# POVWand16.net
KiCad netlist of a schematic drawn in EAGLE
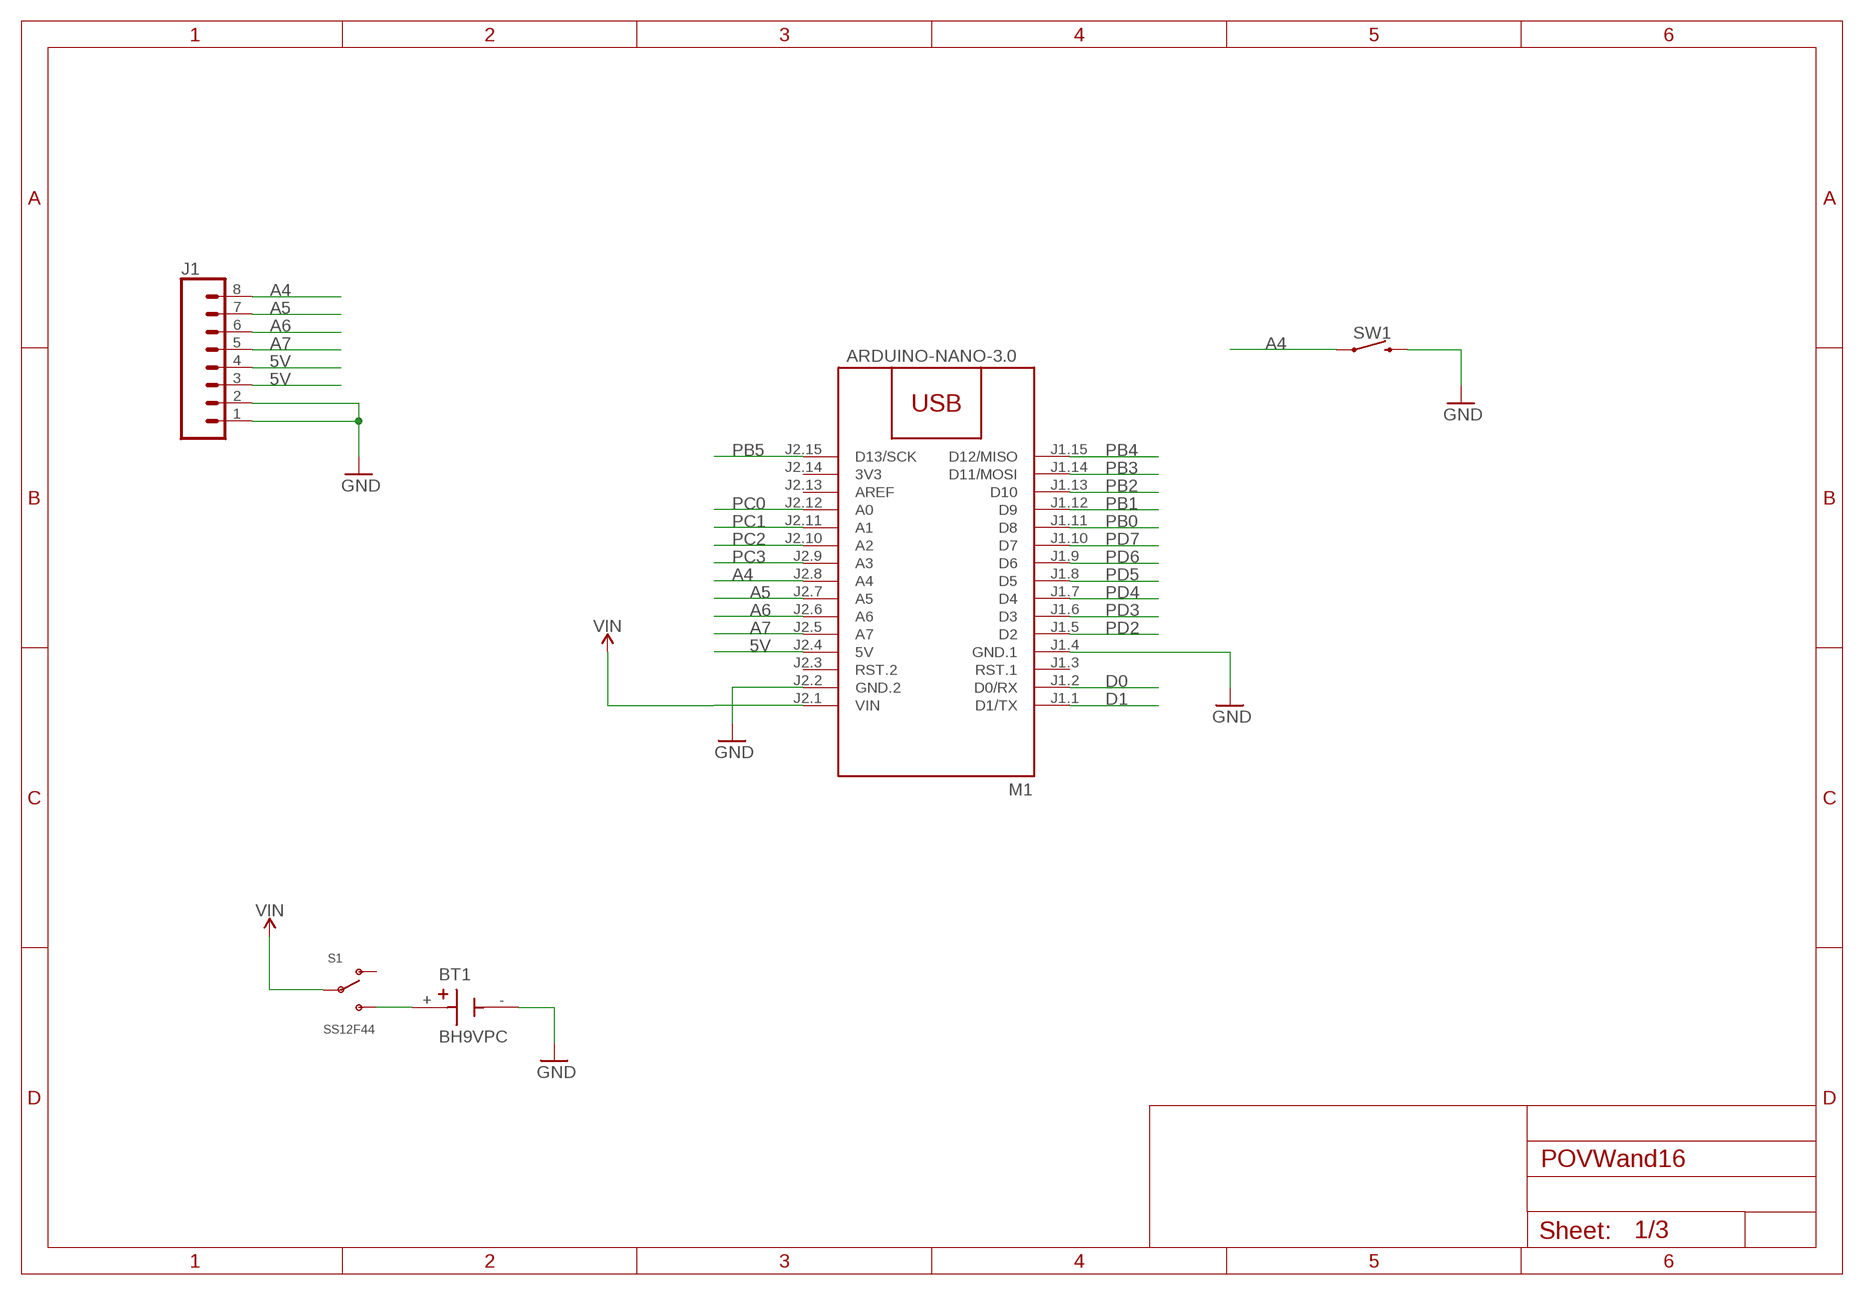
[diagram p0: schematic, sheet 1]
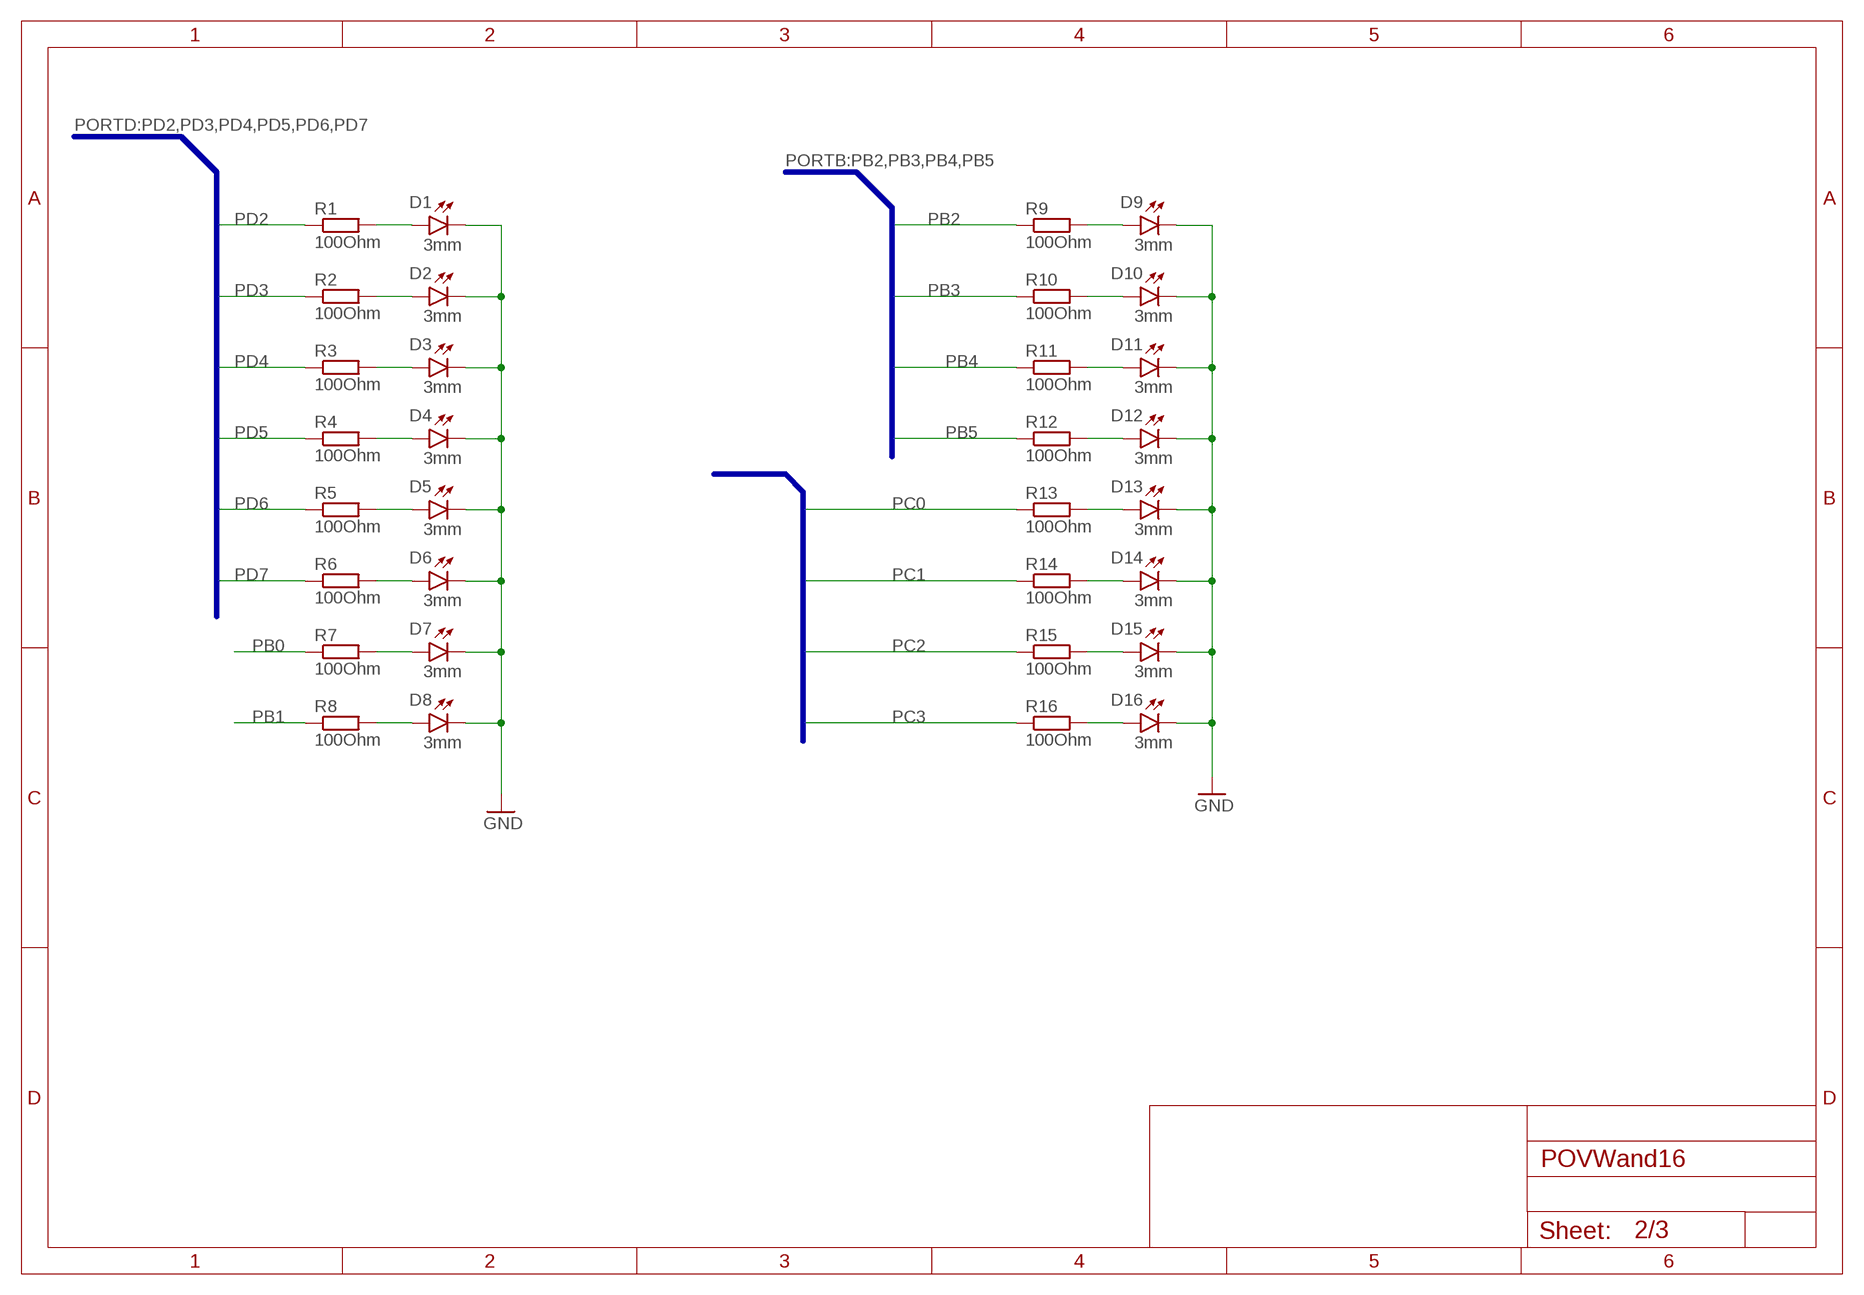
[diagram p1: schematic, sheet 2]
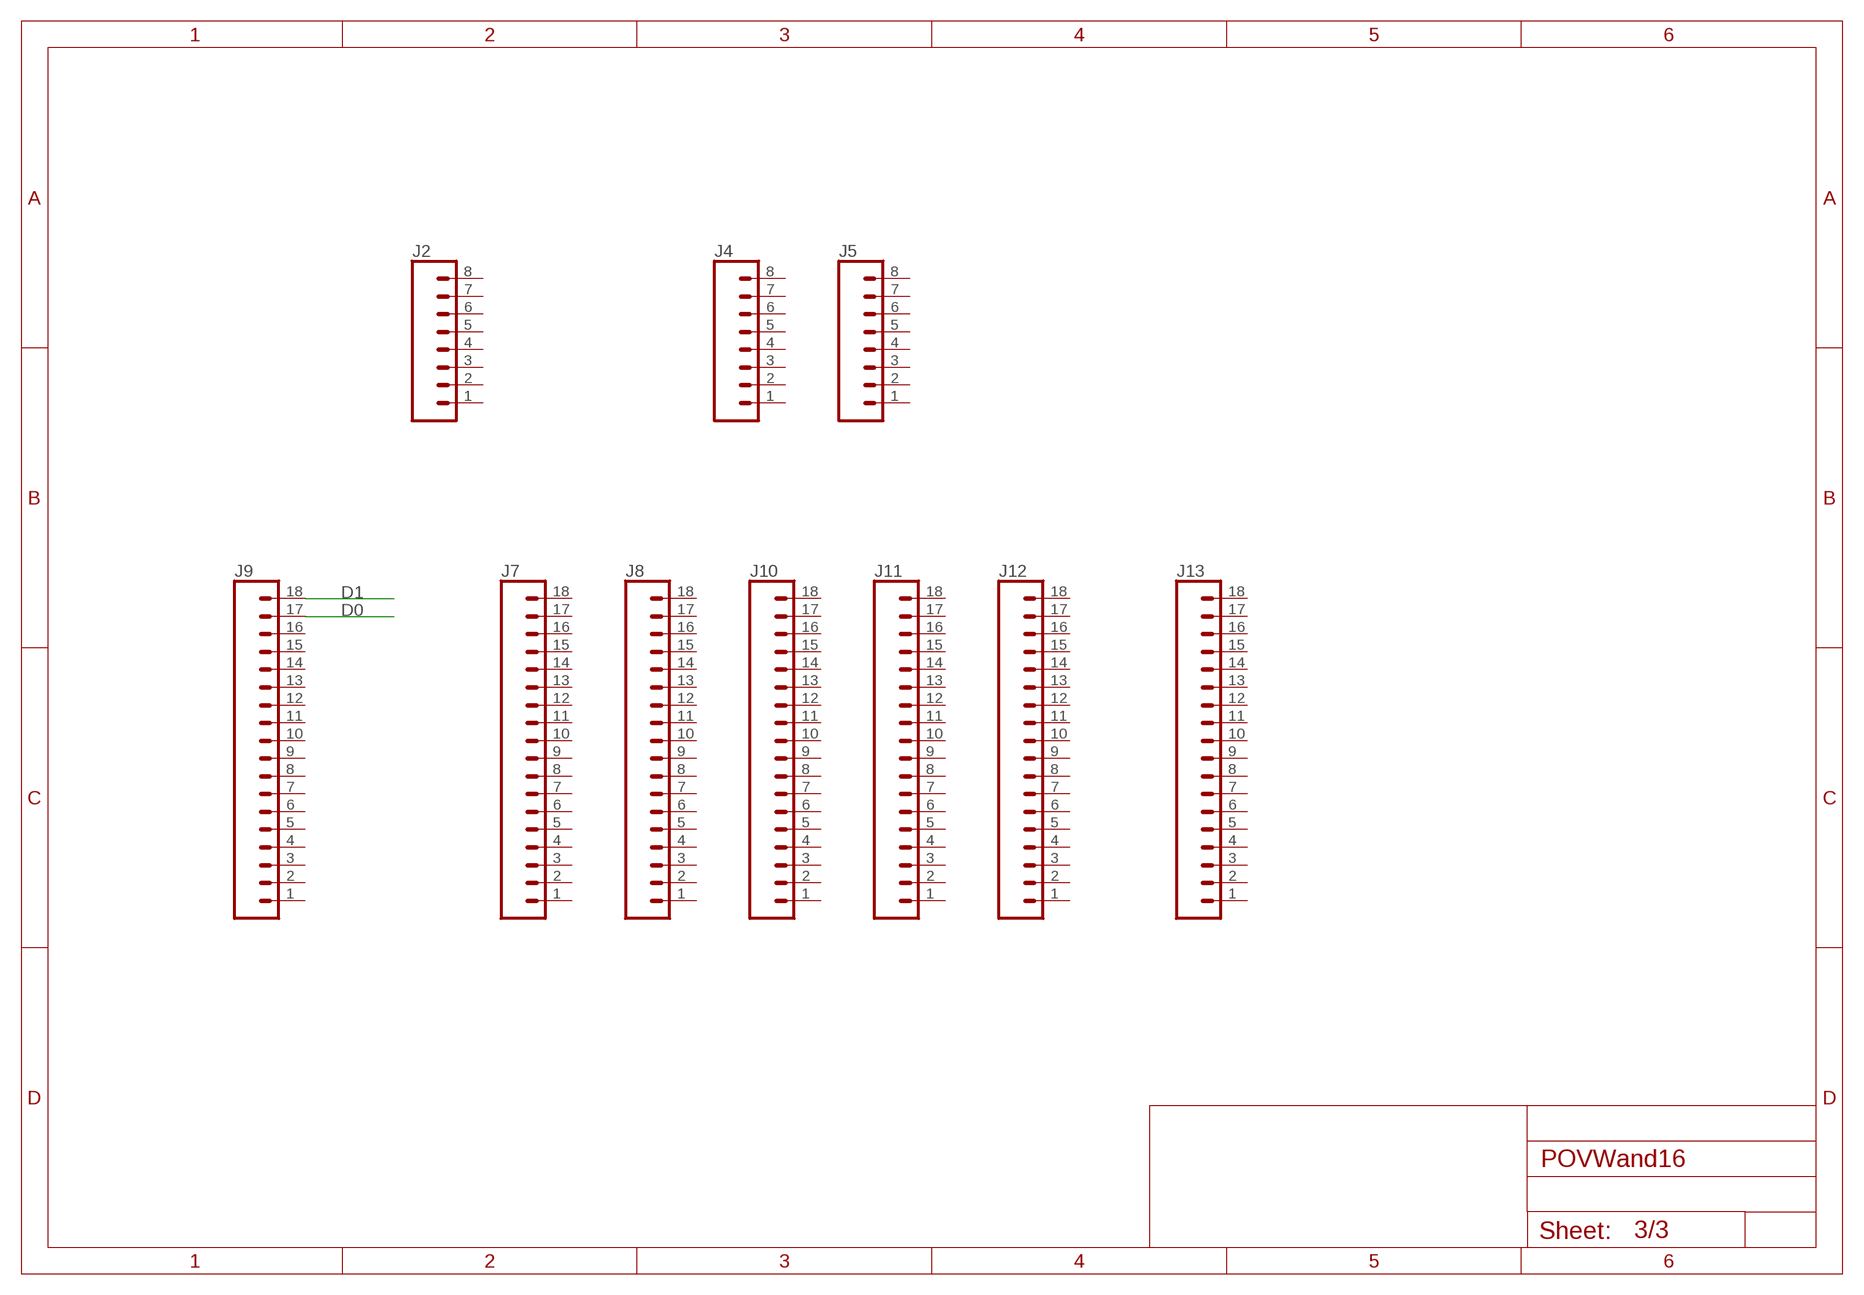
[diagram p2: schematic, sheet 3]

(export (version "E")
  (design (tool "Eeschema 10.0.6"))
  (components
    (comp (ref "BT1")
      (value "BH9VPC")
      (footprint "eagle-import:BAT_BH9VPC")
      (fields (field (name "MF") "MPD _Memory"))
      (libsource (lib "eagle-import") (part "BH9VPC"))
    )
    (comp (ref "J1")
      (value "CONN_08\"")
      (footprint "eagle-import:1X08")
      (libsource (lib "eagle-import") (part "CONN_08{dblquote}"))
    )
    (comp (ref "M1")
      (value "ARDUINO-NANO-3.0")
      (footprint "eagle-import:ARDUINO-NANO-3.0")
      (libsource (lib "eagle-import") (part "ARDUINO-NANO-3.0"))
    )
    (comp (ref "S1")
      (value "SS12F44")
      (footprint "eagle-import:SS12F44G5")
      (fields (field (name "MPN") "SS12F44G5"))
      (libsource (lib "eagle-import") (part "SS12F44"))
    )
    (comp (ref "SW1")
      (value "MOMENTARY-SWITCH-SPST_6X6MM")
      (footprint "eagle-import:TACT_SW_PTH_6.0MM")
      (fields (field (name "MF") "C&K") (field (name "MPN") "PTS645SM43-2 LFS"))
      (libsource (lib "eagle-import") (part "MOMENTARY-SWITCH-SPST_6X6MM"))
    )
    (comp (ref "J2")
      (value "CONN_08\"")
      (footprint "eagle-import:1X08")
      (libsource (lib "eagle-import") (part "CONN_08{dblquote}"))
    )
    (comp (ref "J4")
      (value "CONN_08\"")
      (footprint "eagle-import:1X08")
      (libsource (lib "eagle-import") (part "CONN_08{dblquote}"))
    )
    (comp (ref "J5")
      (value "CONN_08\"")
      (footprint "eagle-import:1X08")
      (libsource (lib "eagle-import") (part "CONN_08{dblquote}"))
    )
    (comp (ref "J7")
      (value "CONN_18")
      (footprint "eagle-import:1X18")
      (libsource (lib "eagle-import") (part "CONN_18"))
    )
    (comp (ref "J8")
      (value "CONN_18")
      (footprint "eagle-import:1X18")
      (libsource (lib "eagle-import") (part "CONN_18"))
    )
    (comp (ref "J9")
      (value "CONN_18")
      (footprint "eagle-import:1X18")
      (libsource (lib "eagle-import") (part "CONN_18"))
    )
    (comp (ref "J10")
      (value "CONN_18")
      (footprint "eagle-import:1X18")
      (libsource (lib "eagle-import") (part "CONN_18"))
    )
    (comp (ref "J11")
      (value "CONN_18")
      (footprint "eagle-import:1X18")
      (libsource (lib "eagle-import") (part "CONN_18"))
    )
    (comp (ref "J12")
      (value "CONN_18")
      (footprint "eagle-import:1X18")
      (libsource (lib "eagle-import") (part "CONN_18"))
    )
    (comp (ref "J13")
      (value "CONN_18")
      (footprint "eagle-import:1X18")
      (libsource (lib "eagle-import") (part "CONN_18"))
    )
    (comp (ref "D1")
      (value "3mm")
      (footprint "eagle-import:LED3MM")
      (libsource (lib "eagle-import") (part "LED_T/H_RADIAL_3MM"))
    )
    (comp (ref "D2")
      (value "3mm")
      (footprint "eagle-import:LED3MM")
      (libsource (lib "eagle-import") (part "LED_T/H_RADIAL_3MM"))
    )
    (comp (ref "D3")
      (value "3mm")
      (footprint "eagle-import:LED3MM")
      (libsource (lib "eagle-import") (part "LED_T/H_RADIAL_3MM"))
    )
    (comp (ref "D4")
      (value "3mm")
      (footprint "eagle-import:LED3MM")
      (libsource (lib "eagle-import") (part "LED_T/H_RADIAL_3MM"))
    )
    (comp (ref "D5")
      (value "3mm")
      (footprint "eagle-import:LED3MM")
      (libsource (lib "eagle-import") (part "LED_T/H_RADIAL_3MM"))
    )
    (comp (ref "D6")
      (value "3mm")
      (footprint "eagle-import:LED3MM")
      (libsource (lib "eagle-import") (part "LED_T/H_RADIAL_3MM"))
    )
    (comp (ref "D7")
      (value "3mm")
      (footprint "eagle-import:LED3MM")
      (libsource (lib "eagle-import") (part "LED_T/H_RADIAL_3MM"))
    )
    (comp (ref "D8")
      (value "3mm")
      (footprint "eagle-import:LED3MM")
      (libsource (lib "eagle-import") (part "LED_T/H_RADIAL_3MM"))
    )
    (comp (ref "D9")
      (value "3mm")
      (footprint "eagle-import:LED3MM")
      (libsource (lib "eagle-import") (part "LED_T/H_RADIAL_3MM"))
    )
    (comp (ref "D10")
      (value "3mm")
      (footprint "eagle-import:LED3MM")
      (libsource (lib "eagle-import") (part "LED_T/H_RADIAL_3MM"))
    )
    (comp (ref "D11")
      (value "3mm")
      (footprint "eagle-import:LED3MM")
      (libsource (lib "eagle-import") (part "LED_T/H_RADIAL_3MM"))
    )
    (comp (ref "D12")
      (value "3mm")
      (footprint "eagle-import:LED3MM")
      (libsource (lib "eagle-import") (part "LED_T/H_RADIAL_3MM"))
    )
    (comp (ref "D13")
      (value "3mm")
      (footprint "eagle-import:LED3MM")
      (libsource (lib "eagle-import") (part "LED_T/H_RADIAL_3MM"))
    )
    (comp (ref "D14")
      (value "3mm")
      (footprint "eagle-import:LED3MM")
      (libsource (lib "eagle-import") (part "LED_T/H_RADIAL_3MM"))
    )
    (comp (ref "D15")
      (value "3mm")
      (footprint "eagle-import:LED3MM")
      (libsource (lib "eagle-import") (part "LED_T/H_RADIAL_3MM"))
    )
    (comp (ref "D16")
      (value "3mm")
      (footprint "eagle-import:LED3MM")
      (libsource (lib "eagle-import") (part "LED_T/H_RADIAL_3MM"))
    )
    (comp (ref "R1")
      (value "100Ohm")
      (footprint "eagle-import:0207_7")
      (libsource (lib "eagle-import") (part "100R_RESISTOR_T/H_0207/7"))
    )
    (comp (ref "R2")
      (value "100Ohm")
      (footprint "eagle-import:0207_7")
      (libsource (lib "eagle-import") (part "100R_RESISTOR_T/H_0207/7"))
    )
    (comp (ref "R3")
      (value "100Ohm")
      (footprint "eagle-import:0207_7")
      (libsource (lib "eagle-import") (part "100R_RESISTOR_T/H_0207/7"))
    )
    (comp (ref "R4")
      (value "100Ohm")
      (footprint "eagle-import:0207_7")
      (libsource (lib "eagle-import") (part "100R_RESISTOR_T/H_0207/7"))
    )
    (comp (ref "R5")
      (value "100Ohm")
      (footprint "eagle-import:0207_7")
      (libsource (lib "eagle-import") (part "100R_RESISTOR_T/H_0207/7"))
    )
    (comp (ref "R6")
      (value "100Ohm")
      (footprint "eagle-import:0207_7")
      (libsource (lib "eagle-import") (part "100R_RESISTOR_T/H_0207/7"))
    )
    (comp (ref "R7")
      (value "100Ohm")
      (footprint "eagle-import:0207_7")
      (libsource (lib "eagle-import") (part "100R_RESISTOR_T/H_0207/7"))
    )
    (comp (ref "R8")
      (value "100Ohm")
      (footprint "eagle-import:0207_7")
      (libsource (lib "eagle-import") (part "100R_RESISTOR_T/H_0207/7"))
    )
    (comp (ref "R9")
      (value "100Ohm")
      (footprint "eagle-import:0207_7")
      (libsource (lib "eagle-import") (part "100R_RESISTOR_T/H_0207/7"))
    )
    (comp (ref "R10")
      (value "100Ohm")
      (footprint "eagle-import:0207_7")
      (libsource (lib "eagle-import") (part "100R_RESISTOR_T/H_0207/7"))
    )
    (comp (ref "R11")
      (value "100Ohm")
      (footprint "eagle-import:0207_7")
      (libsource (lib "eagle-import") (part "100R_RESISTOR_T/H_0207/7"))
    )
    (comp (ref "R12")
      (value "100Ohm")
      (footprint "eagle-import:0207_7")
      (libsource (lib "eagle-import") (part "100R_RESISTOR_T/H_0207/7"))
    )
    (comp (ref "R13")
      (value "100Ohm")
      (footprint "eagle-import:0207_7")
      (libsource (lib "eagle-import") (part "100R_RESISTOR_T/H_0207/7"))
    )
    (comp (ref "R14")
      (value "100Ohm")
      (footprint "eagle-import:0207_7")
      (libsource (lib "eagle-import") (part "100R_RESISTOR_T/H_0207/7"))
    )
    (comp (ref "R15")
      (value "100Ohm")
      (footprint "eagle-import:0207_7")
      (libsource (lib "eagle-import") (part "100R_RESISTOR_T/H_0207/7"))
    )
    (comp (ref "R16")
      (value "100Ohm")
      (footprint "eagle-import:0207_7")
      (libsource (lib "eagle-import") (part "100R_RESISTOR_T/H_0207/7"))
    )
  )
  (nets
    (net (code "5") (name "3V3") (class "Default")
      (node (ref "M1") (pin "J2.14") (pinfunction "3V3_J2.14") (pintype "power_in"))
    )
    (net (code "6") (name "5V") (class "Default")
      (node (ref "J1") (pin "3") (pinfunction "3_3") (pintype "passive"))
      (node (ref "J1") (pin "4") (pinfunction "4_4") (pintype "passive"))
      (node (ref "M1") (pin "J2.4") (pinfunction "5V_J2.4") (pintype "power_in"))
    )
    (net (code "7") (name "A4") (class "Default")
      (node (ref "J1") (pin "8") (pinfunction "8_8") (pintype "passive"))
      (node (ref "M1") (pin "J2.8") (pinfunction "A4_J2.8") (pintype "bidirectional"))
      (node (ref "SW1") (pin "1") (pinfunction "1_1") (pintype "passive"))
      (node (ref "SW1") (pin "2") (pinfunction "1_2") (pintype "passive"))
    )
    (net (code "8") (name "A5") (class "Default")
      (node (ref "J1") (pin "7") (pinfunction "7_7") (pintype "passive"))
      (node (ref "M1") (pin "J2.7") (pinfunction "A5_J2.7") (pintype "bidirectional"))
    )
    (net (code "9") (name "A6") (class "Default")
      (node (ref "J1") (pin "6") (pinfunction "6_6") (pintype "passive"))
      (node (ref "M1") (pin "J2.6") (pinfunction "A6_J2.6") (pintype "bidirectional"))
    )
    (net (code "10") (name "A7") (class "Default")
      (node (ref "J1") (pin "5") (pinfunction "5_5") (pintype "passive"))
      (node (ref "M1") (pin "J2.5") (pinfunction "A7_J2.5") (pintype "bidirectional"))
    )
    (net (code "11") (name "D0") (class "Default")
      (node (ref "J9") (pin "17") (pinfunction "17_17") (pintype "passive"))
      (node (ref "M1") (pin "J1.2") (pinfunction "D0/RX_J1.2") (pintype "bidirectional"))
    )
    (net (code "12") (name "D1") (class "Default")
      (node (ref "J9") (pin "18") (pinfunction "18_18") (pintype "passive"))
      (node (ref "M1") (pin "J1.1") (pinfunction "D1/TX_J1.1") (pintype "bidirectional"))
    )
    (net (code "13") (name "GND") (class "Default")
      (node (ref "BT1") (pin "-") (pinfunction "-_-") (pintype "passive"))
      (node (ref "D1") (pin "K") (pinfunction "C_K") (pintype "passive"))
      (node (ref "D10") (pin "K") (pinfunction "C_K") (pintype "passive"))
      (node (ref "D11") (pin "K") (pinfunction "C_K") (pintype "passive"))
      (node (ref "D12") (pin "K") (pinfunction "C_K") (pintype "passive"))
      (node (ref "D13") (pin "K") (pinfunction "C_K") (pintype "passive"))
      (node (ref "D14") (pin "K") (pinfunction "C_K") (pintype "passive"))
      (node (ref "D15") (pin "K") (pinfunction "C_K") (pintype "passive"))
      (node (ref "D16") (pin "K") (pinfunction "C_K") (pintype "passive"))
      (node (ref "D2") (pin "K") (pinfunction "C_K") (pintype "passive"))
      (node (ref "D3") (pin "K") (pinfunction "C_K") (pintype "passive"))
      (node (ref "D4") (pin "K") (pinfunction "C_K") (pintype "passive"))
      (node (ref "D5") (pin "K") (pinfunction "C_K") (pintype "passive"))
      (node (ref "D6") (pin "K") (pinfunction "C_K") (pintype "passive"))
      (node (ref "D7") (pin "K") (pinfunction "C_K") (pintype "passive"))
      (node (ref "D8") (pin "K") (pinfunction "C_K") (pintype "passive"))
      (node (ref "D9") (pin "K") (pinfunction "C_K") (pintype "passive"))
      (node (ref "J1") (pin "1") (pinfunction "1_1") (pintype "passive"))
      (node (ref "J1") (pin "2") (pinfunction "2_2") (pintype "passive"))
      (node (ref "M1") (pin "J1.4") (pinfunction "GND.1_J1.4") (pintype "power_in"))
      (node (ref "M1") (pin "J2.2") (pinfunction "GND.2_J2.2") (pintype "power_in"))
      (node (ref "SW1") (pin "3") (pinfunction "2_3") (pintype "passive"))
      (node (ref "SW1") (pin "4") (pinfunction "2_4") (pintype "passive"))
    )
    (net (code "14") (name "Net-(D1-PadA)") (class "Default")
      (node (ref "D1") (pin "A") (pinfunction "A_A") (pintype "passive"))
      (node (ref "R1") (pin "2") (pinfunction "2_2") (pintype "passive"))
    )
    (net (code "15") (name "Net-(D2-PadA)") (class "Default")
      (node (ref "D2") (pin "A") (pinfunction "A_A") (pintype "passive"))
      (node (ref "R2") (pin "2") (pinfunction "2_2") (pintype "passive"))
    )
    (net (code "16") (name "Net-(D3-PadA)") (class "Default")
      (node (ref "D3") (pin "A") (pinfunction "A_A") (pintype "passive"))
      (node (ref "R3") (pin "2") (pinfunction "2_2") (pintype "passive"))
    )
    (net (code "17") (name "Net-(D4-PadA)") (class "Default")
      (node (ref "D4") (pin "A") (pinfunction "A_A") (pintype "passive"))
      (node (ref "R4") (pin "2") (pinfunction "2_2") (pintype "passive"))
    )
    (net (code "18") (name "Net-(D5-PadA)") (class "Default")
      (node (ref "D5") (pin "A") (pinfunction "A_A") (pintype "passive"))
      (node (ref "R5") (pin "2") (pinfunction "2_2") (pintype "passive"))
    )
    (net (code "19") (name "Net-(D6-PadA)") (class "Default")
      (node (ref "D6") (pin "A") (pinfunction "A_A") (pintype "passive"))
      (node (ref "R6") (pin "2") (pinfunction "2_2") (pintype "passive"))
    )
    (net (code "20") (name "Net-(D7-PadA)") (class "Default")
      (node (ref "D7") (pin "A") (pinfunction "A_A") (pintype "passive"))
      (node (ref "R7") (pin "2") (pinfunction "2_2") (pintype "passive"))
    )
    (net (code "21") (name "Net-(D8-PadA)") (class "Default")
      (node (ref "D8") (pin "A") (pinfunction "A_A") (pintype "passive"))
      (node (ref "R8") (pin "2") (pinfunction "2_2") (pintype "passive"))
    )
    (net (code "22") (name "Net-(D9-PadA)") (class "Default")
      (node (ref "D9") (pin "A") (pinfunction "A_A") (pintype "passive"))
      (node (ref "R9") (pin "2") (pinfunction "2_2") (pintype "passive"))
    )
    (net (code "23") (name "Net-(D10-PadA)") (class "Default")
      (node (ref "D10") (pin "A") (pinfunction "A_A") (pintype "passive"))
      (node (ref "R10") (pin "2") (pinfunction "2_2") (pintype "passive"))
    )
    (net (code "24") (name "Net-(D11-PadA)") (class "Default")
      (node (ref "D11") (pin "A") (pinfunction "A_A") (pintype "passive"))
      (node (ref "R11") (pin "2") (pinfunction "2_2") (pintype "passive"))
    )
    (net (code "25") (name "Net-(D12-PadA)") (class "Default")
      (node (ref "D12") (pin "A") (pinfunction "A_A") (pintype "passive"))
      (node (ref "R12") (pin "2") (pinfunction "2_2") (pintype "passive"))
    )
    (net (code "26") (name "Net-(D13-PadA)") (class "Default")
      (node (ref "D13") (pin "A") (pinfunction "A_A") (pintype "passive"))
      (node (ref "R13") (pin "2") (pinfunction "2_2") (pintype "passive"))
    )
    (net (code "27") (name "Net-(D14-PadA)") (class "Default")
      (node (ref "D14") (pin "A") (pinfunction "A_A") (pintype "passive"))
      (node (ref "R14") (pin "2") (pinfunction "2_2") (pintype "passive"))
    )
    (net (code "28") (name "Net-(D15-PadA)") (class "Default")
      (node (ref "D15") (pin "A") (pinfunction "A_A") (pintype "passive"))
      (node (ref "R15") (pin "2") (pinfunction "2_2") (pintype "passive"))
    )
    (net (code "29") (name "Net-(D16-PadA)") (class "Default")
      (node (ref "D16") (pin "A") (pinfunction "A_A") (pintype "passive"))
      (node (ref "R16") (pin "2") (pinfunction "2_2") (pintype "passive"))
    )
    (net (code "30") (name "Net-(S1-S)") (class "Default")
      (node (ref "BT1") (pin "+") (pinfunction "+_+") (pintype "passive"))
      (node (ref "S1") (pin "3") (pinfunction "S_3") (pintype "passive"))
    )
    (net (code "31") (name "PB0") (class "Default")
      (node (ref "M1") (pin "J1.11") (pinfunction "D8_J1.11") (pintype "bidirectional"))
      (node (ref "R7") (pin "1") (pinfunction "1_1") (pintype "passive"))
    )
    (net (code "32") (name "PB1") (class "Default")
      (node (ref "M1") (pin "J1.12") (pinfunction "D9_J1.12") (pintype "bidirectional"))
      (node (ref "R8") (pin "1") (pinfunction "1_1") (pintype "passive"))
    )
    (net (code "33") (name "PB2") (class "Default")
      (node (ref "M1") (pin "J1.13") (pinfunction "D10_J1.13") (pintype "bidirectional"))
      (node (ref "R9") (pin "1") (pinfunction "1_1") (pintype "passive"))
    )
    (net (code "34") (name "PB3") (class "Default")
      (node (ref "M1") (pin "J1.14") (pinfunction "D11/MOSI_J1.14") (pintype "bidirectional"))
      (node (ref "R10") (pin "1") (pinfunction "1_1") (pintype "passive"))
    )
    (net (code "35") (name "PB4") (class "Default")
      (node (ref "M1") (pin "J1.15") (pinfunction "D12/MISO_J1.15") (pintype "bidirectional"))
      (node (ref "R11") (pin "1") (pinfunction "1_1") (pintype "passive"))
    )
    (net (code "36") (name "PB5") (class "Default")
      (node (ref "M1") (pin "J2.15") (pinfunction "D13/SCK_J2.15") (pintype "bidirectional"))
      (node (ref "R12") (pin "1") (pinfunction "1_1") (pintype "passive"))
    )
    (net (code "37") (name "PC0") (class "Default")
      (node (ref "M1") (pin "J2.12") (pinfunction "A0_J2.12") (pintype "bidirectional"))
      (node (ref "R13") (pin "1") (pinfunction "1_1") (pintype "passive"))
    )
    (net (code "38") (name "PC1") (class "Default")
      (node (ref "M1") (pin "J2.11") (pinfunction "A1_J2.11") (pintype "bidirectional"))
      (node (ref "R14") (pin "1") (pinfunction "1_1") (pintype "passive"))
    )
    (net (code "39") (name "PC2") (class "Default")
      (node (ref "M1") (pin "J2.10") (pinfunction "A2_J2.10") (pintype "bidirectional"))
      (node (ref "R15") (pin "1") (pinfunction "1_1") (pintype "passive"))
    )
    (net (code "40") (name "PC3") (class "Default")
      (node (ref "M1") (pin "J2.9") (pinfunction "A3_J2.9") (pintype "bidirectional"))
      (node (ref "R16") (pin "1") (pinfunction "1_1") (pintype "passive"))
    )
    (net (code "41") (name "PD2") (class "Default")
      (node (ref "M1") (pin "J1.5") (pinfunction "D2_J1.5") (pintype "bidirectional"))
      (node (ref "R1") (pin "1") (pinfunction "1_1") (pintype "passive"))
    )
    (net (code "42") (name "PD3") (class "Default")
      (node (ref "M1") (pin "J1.6") (pinfunction "D3_J1.6") (pintype "bidirectional"))
      (node (ref "R2") (pin "1") (pinfunction "1_1") (pintype "passive"))
    )
    (net (code "43") (name "PD4") (class "Default")
      (node (ref "M1") (pin "J1.7") (pinfunction "D4_J1.7") (pintype "bidirectional"))
      (node (ref "R3") (pin "1") (pinfunction "1_1") (pintype "passive"))
    )
    (net (code "44") (name "PD5") (class "Default")
      (node (ref "M1") (pin "J1.8") (pinfunction "D5_J1.8") (pintype "bidirectional"))
      (node (ref "R4") (pin "1") (pinfunction "1_1") (pintype "passive"))
    )
    (net (code "45") (name "PD6") (class "Default")
      (node (ref "M1") (pin "J1.9") (pinfunction "D6_J1.9") (pintype "bidirectional"))
      (node (ref "R5") (pin "1") (pinfunction "1_1") (pintype "passive"))
    )
    (net (code "46") (name "PD7") (class "Default")
      (node (ref "M1") (pin "J1.10") (pinfunction "D7_J1.10") (pintype "bidirectional"))
      (node (ref "R6") (pin "1") (pinfunction "1_1") (pintype "passive"))
    )
    (net (code "47") (name "VIN") (class "Default")
      (node (ref "M1") (pin "J2.1") (pinfunction "VIN_J2.1") (pintype "power_in"))
      (node (ref "S1") (pin "2") (pinfunction "P_2") (pintype "passive"))
    )
    (net (code "48") (name "unconnected-(J2-Pad1)") (class "Default")
      (node (ref "J2") (pin "1") (pinfunction "1_1") (pintype "passive"))
    )
    (net (code "49") (name "unconnected-(J2-Pad2)") (class "Default")
      (node (ref "J2") (pin "2") (pinfunction "2_2") (pintype "passive"))
    )
    (net (code "50") (name "unconnected-(J2-Pad3)") (class "Default")
      (node (ref "J2") (pin "3") (pinfunction "3_3") (pintype "passive"))
    )
    (net (code "51") (name "unconnected-(J2-Pad4)") (class "Default")
      (node (ref "J2") (pin "4") (pinfunction "4_4") (pintype "passive"))
    )
    (net (code "52") (name "unconnected-(J2-Pad5)") (class "Default")
      (node (ref "J2") (pin "5") (pinfunction "5_5") (pintype "passive"))
    )
    (net (code "53") (name "unconnected-(J2-Pad6)") (class "Default")
      (node (ref "J2") (pin "6") (pinfunction "6_6") (pintype "passive"))
    )
    (net (code "54") (name "unconnected-(J2-Pad7)") (class "Default")
      (node (ref "J2") (pin "7") (pinfunction "7_7") (pintype "passive"))
    )
    (net (code "55") (name "unconnected-(J2-Pad8)") (class "Default")
      (node (ref "J2") (pin "8") (pinfunction "8_8") (pintype "passive"))
    )
    (net (code "56") (name "unconnected-(J4-Pad1)") (class "Default")
      (node (ref "J4") (pin "1") (pinfunction "1_1") (pintype "passive"))
    )
    (net (code "57") (name "unconnected-(J4-Pad2)") (class "Default")
      (node (ref "J4") (pin "2") (pinfunction "2_2") (pintype "passive"))
    )
    (net (code "58") (name "unconnected-(J4-Pad3)") (class "Default")
      (node (ref "J4") (pin "3") (pinfunction "3_3") (pintype "passive"))
    )
    (net (code "59") (name "unconnected-(J4-Pad4)") (class "Default")
      (node (ref "J4") (pin "4") (pinfunction "4_4") (pintype "passive"))
    )
    (net (code "60") (name "unconnected-(J4-Pad5)") (class "Default")
      (node (ref "J4") (pin "5") (pinfunction "5_5") (pintype "passive"))
    )
    (net (code "61") (name "unconnected-(J4-Pad6)") (class "Default")
      (node (ref "J4") (pin "6") (pinfunction "6_6") (pintype "passive"))
    )
    (net (code "62") (name "unconnected-(J4-Pad7)") (class "Default")
      (node (ref "J4") (pin "7") (pinfunction "7_7") (pintype "passive"))
    )
    (net (code "63") (name "unconnected-(J4-Pad8)") (class "Default")
      (node (ref "J4") (pin "8") (pinfunction "8_8") (pintype "passive"))
    )
    (net (code "64") (name "unconnected-(J5-Pad1)") (class "Default")
      (node (ref "J5") (pin "1") (pinfunction "1_1") (pintype "passive"))
    )
    (net (code "65") (name "unconnected-(J5-Pad2)") (class "Default")
      (node (ref "J5") (pin "2") (pinfunction "2_2") (pintype "passive"))
    )
    (net (code "66") (name "unconnected-(J5-Pad3)") (class "Default")
      (node (ref "J5") (pin "3") (pinfunction "3_3") (pintype "passive"))
    )
    (net (code "67") (name "unconnected-(J5-Pad4)") (class "Default")
      (node (ref "J5") (pin "4") (pinfunction "4_4") (pintype "passive"))
    )
    (net (code "68") (name "unconnected-(J5-Pad5)") (class "Default")
      (node (ref "J5") (pin "5") (pinfunction "5_5") (pintype "passive"))
    )
    (net (code "69") (name "unconnected-(J5-Pad6)") (class "Default")
      (node (ref "J5") (pin "6") (pinfunction "6_6") (pintype "passive"))
    )
    (net (code "70") (name "unconnected-(J5-Pad7)") (class "Default")
      (node (ref "J5") (pin "7") (pinfunction "7_7") (pintype "passive"))
    )
    (net (code "71") (name "unconnected-(J5-Pad8)") (class "Default")
      (node (ref "J5") (pin "8") (pinfunction "8_8") (pintype "passive"))
    )
    (net (code "72") (name "unconnected-(J7-Pad1)") (class "Default")
      (node (ref "J7") (pin "1") (pinfunction "1_1") (pintype "passive"))
    )
    (net (code "73") (name "unconnected-(J7-Pad2)") (class "Default")
      (node (ref "J7") (pin "2") (pinfunction "2_2") (pintype "passive"))
    )
    (net (code "74") (name "unconnected-(J7-Pad3)") (class "Default")
      (node (ref "J7") (pin "3") (pinfunction "3_3") (pintype "passive"))
    )
    (net (code "75") (name "unconnected-(J7-Pad4)") (class "Default")
      (node (ref "J7") (pin "4") (pinfunction "4_4") (pintype "passive"))
    )
    (net (code "76") (name "unconnected-(J7-Pad5)") (class "Default")
      (node (ref "J7") (pin "5") (pinfunction "5_5") (pintype "passive"))
    )
    (net (code "77") (name "unconnected-(J7-Pad6)") (class "Default")
      (node (ref "J7") (pin "6") (pinfunction "6_6") (pintype "passive"))
    )
    (net (code "78") (name "unconnected-(J7-Pad7)") (class "Default")
      (node (ref "J7") (pin "7") (pinfunction "7_7") (pintype "passive"))
    )
    (net (code "79") (name "unconnected-(J7-Pad8)") (class "Default")
      (node (ref "J7") (pin "8") (pinfunction "8_8") (pintype "passive"))
    )
    (net (code "80") (name "unconnected-(J7-Pad9)") (class "Default")
      (node (ref "J7") (pin "9") (pinfunction "9_9") (pintype "passive"))
    )
    (net (code "81") (name "unconnected-(J7-Pad10)") (class "Default")
      (node (ref "J7") (pin "10") (pinfunction "10_10") (pintype "passive"))
    )
    (net (code "82") (name "unconnected-(J7-Pad11)") (class "Default")
      (node (ref "J7") (pin "11") (pinfunction "11_11") (pintype "passive"))
    )
    (net (code "83") (name "unconnected-(J7-Pad12)") (class "Default")
      (node (ref "J7") (pin "12") (pinfunction "12_12") (pintype "passive"))
    )
    (net (code "84") (name "unconnected-(J7-Pad13)") (class "Default")
      (node (ref "J7") (pin "13") (pinfunction "13_13") (pintype "passive"))
    )
    (net (code "85") (name "unconnected-(J7-Pad14)") (class "Default")
      (node (ref "J7") (pin "14") (pinfunction "14_14") (pintype "passive"))
    )
    (net (code "86") (name "unconnected-(J7-Pad15)") (class "Default")
      (node (ref "J7") (pin "15") (pinfunction "15_15") (pintype "passive"))
    )
    (net (code "87") (name "unconnected-(J7-Pad16)") (class "Default")
      (node (ref "J7") (pin "16") (pinfunction "16_16") (pintype "passive"))
    )
    (net (code "88") (name "unconnected-(J7-Pad17)") (class "Default")
      (node (ref "J7") (pin "17") (pinfunction "17_17") (pintype "passive"))
    )
    (net (code "89") (name "unconnected-(J7-Pad18)") (class "Default")
      (node (ref "J7") (pin "18") (pinfunction "18_18") (pintype "passive"))
    )
    (net (code "90") (name "unconnected-(J8-Pad1)") (class "Default")
      (node (ref "J8") (pin "1") (pinfunction "1_1") (pintype "passive"))
    )
    (net (code "91") (name "unconnected-(J8-Pad2)") (class "Default")
      (node (ref "J8") (pin "2") (pinfunction "2_2") (pintype "passive"))
    )
    (net (code "92") (name "unconnected-(J8-Pad3)") (class "Default")
      (node (ref "J8") (pin "3") (pinfunction "3_3") (pintype "passive"))
    )
    (net (code "93") (name "unconnected-(J8-Pad4)") (class "Default")
      (node (ref "J8") (pin "4") (pinfunction "4_4") (pintype "passive"))
    )
    (net (code "94") (name "unconnected-(J8-Pad5)") (class "Default")
      (node (ref "J8") (pin "5") (pinfunction "5_5") (pintype "passive"))
    )
    (net (code "95") (name "unconnected-(J8-Pad6)") (class "Default")
      (node (ref "J8") (pin "6") (pinfunction "6_6") (pintype "passive"))
    )
    (net (code "96") (name "unconnected-(J8-Pad7)") (class "Default")
      (node (ref "J8") (pin "7") (pinfunction "7_7") (pintype "passive"))
    )
    (net (code "97") (name "unconnected-(J8-Pad8)") (class "Default")
      (node (ref "J8") (pin "8") (pinfunction "8_8") (pintype "passive"))
    )
    (net (code "98") (name "unconnected-(J8-Pad9)") (class "Default")
      (node (ref "J8") (pin "9") (pinfunction "9_9") (pintype "passive"))
    )
    (net (code "99") (name "unconnected-(J8-Pad10)") (class "Default")
      (node (ref "J8") (pin "10") (pinfunction "10_10") (pintype "passive"))
    )
    (net (code "100") (name "unconnected-(J8-Pad11)") (class "Default")
      (node (ref "J8") (pin "11") (pinfunction "11_11") (pintype "passive"))
    )
    (net (code "101") (name "unconnected-(J8-Pad12)") (class "Default")
      (node (ref "J8") (pin "12") (pinfunction "12_12") (pintype "passive"))
    )
    (net (code "102") (name "unconnected-(J8-Pad13)") (class "Default")
      (node (ref "J8") (pin "13") (pinfunction "13_13") (pintype "passive"))
    )
    (net (code "103") (name "unconnected-(J8-Pad14)") (class "Default")
      (node (ref "J8") (pin "14") (pinfunction "14_14") (pintype "passive"))
    )
    (net (code "104") (name "unconnected-(J8-Pad15)") (class "Default")
      (node (ref "J8") (pin "15") (pinfunction "15_15") (pintype "passive"))
    )
    (net (code "105") (name "unconnected-(J8-Pad16)") (class "Default")
      (node (ref "J8") (pin "16") (pinfunction "16_16") (pintype "passive"))
    )
    (net (code "106") (name "unconnected-(J8-Pad17)") (class "Default")
      (node (ref "J8") (pin "17") (pinfunction "17_17") (pintype "passive"))
    )
    (net (code "107") (name "unconnected-(J8-Pad18)") (class "Default")
      (node (ref "J8") (pin "18") (pinfunction "18_18") (pintype "passive"))
    )
    (net (code "108") (name "unconnected-(J9-Pad1)") (class "Default")
      (node (ref "J9") (pin "1") (pinfunction "1_1") (pintype "passive"))
    )
    (net (code "109") (name "unconnected-(J9-Pad2)") (class "Default")
      (node (ref "J9") (pin "2") (pinfunction "2_2") (pintype "passive"))
    )
    (net (code "110") (name "unconnected-(J9-Pad3)") (class "Default")
      (node (ref "J9") (pin "3") (pinfunction "3_3") (pintype "passive"))
    )
    (net (code "111") (name "unconnected-(J9-Pad4)") (class "Default")
      (node (ref "J9") (pin "4") (pinfunction "4_4") (pintype "passive"))
    )
    (net (code "112") (name "unconnected-(J9-Pad5)") (class "Default")
      (node (ref "J9") (pin "5") (pinfunction "5_5") (pintype "passive"))
    )
    (net (code "113") (name "unconnected-(J9-Pad6)") (class "Default")
      (node (ref "J9") (pin "6") (pinfunction "6_6") (pintype "passive"))
    )
    (net (code "114") (name "unconnected-(J9-Pad7)") (class "Default")
      (node (ref "J9") (pin "7") (pinfunction "7_7") (pintype "passive"))
    )
    (net (code "115") (name "unconnected-(J9-Pad8)") (class "Default")
      (node (ref "J9") (pin "8") (pinfunction "8_8") (pintype "passive"))
    )
    (net (code "116") (name "unconnected-(J9-Pad9)") (class "Default")
      (node (ref "J9") (pin "9") (pinfunction "9_9") (pintype "passive"))
    )
    (net (code "117") (name "unconnected-(J9-Pad10)") (class "Default")
      (node (ref "J9") (pin "10") (pinfunction "10_10") (pintype "passive"))
    )
    (net (code "118") (name "unconnected-(J9-Pad11)") (class "Default")
      (node (ref "J9") (pin "11") (pinfunction "11_11") (pintype "passive"))
    )
    (net (code "119") (name "unconnected-(J9-Pad12)") (class "Default")
      (node (ref "J9") (pin "12") (pinfunction "12_12") (pintype "passive"))
    )
    (net (code "120") (name "unconnected-(J9-Pad13)") (class "Default")
      (node (ref "J9") (pin "13") (pinfunction "13_13") (pintype "passive"))
    )
    (net (code "121") (name "unconnected-(J9-Pad14)") (class "Default")
      (node (ref "J9") (pin "14") (pinfunction "14_14") (pintype "passive"))
    )
    (net (code "122") (name "unconnected-(J9-Pad15)") (class "Default")
      (node (ref "J9") (pin "15") (pinfunction "15_15") (pintype "passive"))
    )
    (net (code "123") (name "unconnected-(J9-Pad16)") (class "Default")
      (node (ref "J9") (pin "16") (pinfunction "16_16") (pintype "passive"))
    )
    (net (code "124") (name "unconnected-(J10-Pad1)") (class "Default")
      (node (ref "J10") (pin "1") (pinfunction "1_1") (pintype "passive"))
    )
    (net (code "125") (name "unconnected-(J10-Pad2)") (class "Default")
      (node (ref "J10") (pin "2") (pinfunction "2_2") (pintype "passive"))
    )
    (net (code "126") (name "unconnected-(J10-Pad3)") (class "Default")
      (node (ref "J10") (pin "3") (pinfunction "3_3") (pintype "passive"))
    )
    (net (code "127") (name "unconnected-(J10-Pad4)") (class "Default")
      (node (ref "J10") (pin "4") (pinfunction "4_4") (pintype "passive"))
    )
    (net (code "128") (name "unconnected-(J10-Pad5)") (class "Default")
      (node (ref "J10") (pin "5") (pinfunction "5_5") (pintype "passive"))
    )
    (net (code "129") (name "unconnected-(J10-Pad6)") (class "Default")
      (node (ref "J10") (pin "6") (pinfunction "6_6") (pintype "passive"))
    )
    (net (code "130") (name "unconnected-(J10-Pad7)") (class "Default")
      (node (ref "J10") (pin "7") (pinfunction "7_7") (pintype "passive"))
    )
    (net (code "131") (name "unconnected-(J10-Pad8)") (class "Default")
      (node (ref "J10") (pin "8") (pinfunction "8_8") (pintype "passive"))
    )
    (net (code "132") (name "unconnected-(J10-Pad9)") (class "Default")
      (node (ref "J10") (pin "9") (pinfunction "9_9") (pintype "passive"))
    )
    (net (code "133") (name "unconnected-(J10-Pad10)") (class "Default")
      (node (ref "J10") (pin "10") (pinfunction "10_10") (pintype "passive"))
    )
    (net (code "134") (name "unconnected-(J10-Pad11)") (class "Default")
      (node (ref "J10") (pin "11") (pinfunction "11_11") (pintype "passive"))
    )
    (net (code "135") (name "unconnected-(J10-Pad12)") (class "Default")
      (node (ref "J10") (pin "12") (pinfunction "12_12") (pintype "passive"))
    )
    (net (code "136") (name "unconnected-(J10-Pad13)") (class "Default")
      (node (ref "J10") (pin "13") (pinfunction "13_13") (pintype "passive"))
    )
    (net (code "137") (name "unconnected-(J10-Pad14)") (class "Default")
      (node (ref "J10") (pin "14") (pinfunction "14_14") (pintype "passive"))
    )
    (net (code "138") (name "unconnected-(J10-Pad15)") (class "Default")
      (node (ref "J10") (pin "15") (pinfunction "15_15") (pintype "passive"))
    )
    (net (code "139") (name "unconnected-(J10-Pad16)") (class "Default")
      (node (ref "J10") (pin "16") (pinfunction "16_16") (pintype "passive"))
    )
    (net (code "140") (name "unconnected-(J10-Pad17)") (class "Default")
      (node (ref "J10") (pin "17") (pinfunction "17_17") (pintype "passive"))
    )
    (net (code "141") (name "unconnected-(J10-Pad18)") (class "Default")
      (node (ref "J10") (pin "18") (pinfunction "18_18") (pintype "passive"))
    )
    (net (code "142") (name "unconnected-(J11-Pad1)") (class "Default")
      (node (ref "J11") (pin "1") (pinfunction "1_1") (pintype "passive"))
    )
    (net (code "143") (name "unconnected-(J11-Pad2)") (class "Default")
      (node (ref "J11") (pin "2") (pinfunction "2_2") (pintype "passive"))
    )
    (net (code "144") (name "unconnected-(J11-Pad3)") (class "Default")
      (node (ref "J11") (pin "3") (pinfunction "3_3") (pintype "passive"))
    )
    (net (code "145") (name "unconnected-(J11-Pad4)") (class "Default")
      (node (ref "J11") (pin "4") (pinfunction "4_4") (pintype "passive"))
    )
    (net (code "146") (name "unconnected-(J11-Pad5)") (class "Default")
      (node (ref "J11") (pin "5") (pinfunction "5_5") (pintype "passive"))
    )
    (net (code "147") (name "unconnected-(J11-Pad6)") (class "Default")
      (node (ref "J11") (pin "6") (pinfunction "6_6") (pintype "passive"))
    )
    (net (code "148") (name "unconnected-(J11-Pad7)") (class "Default")
      (node (ref "J11") (pin "7") (pinfunction "7_7") (pintype "passive"))
    )
    (net (code "149") (name "unconnected-(J11-Pad8)") (class "Default")
      (node (ref "J11") (pin "8") (pinfunction "8_8") (pintype "passive"))
    )
    (net (code "150") (name "unconnected-(J11-Pad9)") (class "Default")
      (node (ref "J11") (pin "9") (pinfunction "9_9") (pintype "passive"))
    )
    (net (code "151") (name "unconnected-(J11-Pad10)") (class "Default")
      (node (ref "J11") (pin "10") (pinfunction "10_10") (pintype "passive"))
    )
    (net (code "152") (name "unconnected-(J11-Pad11)") (class "Default")
      (node (ref "J11") (pin "11") (pinfunction "11_11") (pintype "passive"))
    )
    (net (code "153") (name "unconnected-(J11-Pad12)") (class "Default")
      (node (ref "J11") (pin "12") (pinfunction "12_12") (pintype "passive"))
    )
    (net (code "154") (name "unconnected-(J11-Pad13)") (class "Default")
      (node (ref "J11") (pin "13") (pinfunction "13_13") (pintype "passive"))
    )
    (net (code "155") (name "unconnected-(J11-Pad14)") (class "Default")
      (node (ref "J11") (pin "14") (pinfunction "14_14") (pintype "passive"))
    )
    (net (code "156") (name "unconnected-(J11-Pad15)") (class "Default")
      (node (ref "J11") (pin "15") (pinfunction "15_15") (pintype "passive"))
    )
    (net (code "157") (name "unconnected-(J11-Pad16)") (class "Default")
      (node (ref "J11") (pin "16") (pinfunction "16_16") (pintype "passive"))
    )
    (net (code "158") (name "unconnected-(J11-Pad17)") (class "Default")
      (node (ref "J11") (pin "17") (pinfunction "17_17") (pintype "passive"))
    )
    (net (code "159") (name "unconnected-(J11-Pad18)") (class "Default")
      (node (ref "J11") (pin "18") (pinfunction "18_18") (pintype "passive"))
    )
    (net (code "160") (name "unconnected-(J12-Pad1)") (class "Default")
      (node (ref "J12") (pin "1") (pinfunction "1_1") (pintype "passive"))
    )
    (net (code "161") (name "unconnected-(J12-Pad2)") (class "Default")
      (node (ref "J12") (pin "2") (pinfunction "2_2") (pintype "passive"))
    )
    (net (code "162") (name "unconnected-(J12-Pad3)") (class "Default")
      (node (ref "J12") (pin "3") (pinfunction "3_3") (pintype "passive"))
    )
    (net (code "163") (name "unconnected-(J12-Pad4)") (class "Default")
      (node (ref "J12") (pin "4") (pinfunction "4_4") (pintype "passive"))
    )
    (net (code "164") (name "unconnected-(J12-Pad5)") (class "Default")
      (node (ref "J12") (pin "5") (pinfunction "5_5") (pintype "passive"))
    )
    (net (code "165") (name "unconnected-(J12-Pad6)") (class "Default")
      (node (ref "J12") (pin "6") (pinfunction "6_6") (pintype "passive"))
    )
    (net (code "166") (name "unconnected-(J12-Pad7)") (class "Default")
      (node (ref "J12") (pin "7") (pinfunction "7_7") (pintype "passive"))
    )
    (net (code "167") (name "unconnected-(J12-Pad8)") (class "Default")
      (node (ref "J12") (pin "8") (pinfunction "8_8") (pintype "passive"))
    )
    (net (code "168") (name "unconnected-(J12-Pad9)") (class "Default")
      (node (ref "J12") (pin "9") (pinfunction "9_9") (pintype "passive"))
    )
    (net (code "169") (name "unconnected-(J12-Pad10)") (class "Default")
      (node (ref "J12") (pin "10") (pinfunction "10_10") (pintype "passive"))
    )
    (net (code "170") (name "unconnected-(J12-Pad11)") (class "Default")
      (node (ref "J12") (pin "11") (pinfunction "11_11") (pintype "passive"))
    )
    (net (code "171") (name "unconnected-(J12-Pad12)") (class "Default")
      (node (ref "J12") (pin "12") (pinfunction "12_12") (pintype "passive"))
    )
    (net (code "172") (name "unconnected-(J12-Pad13)") (class "Default")
      (node (ref "J12") (pin "13") (pinfunction "13_13") (pintype "passive"))
    )
    (net (code "173") (name "unconnected-(J12-Pad14)") (class "Default")
      (node (ref "J12") (pin "14") (pinfunction "14_14") (pintype "passive"))
    )
    (net (code "174") (name "unconnected-(J12-Pad15)") (class "Default")
      (node (ref "J12") (pin "15") (pinfunction "15_15") (pintype "passive"))
    )
    (net (code "175") (name "unconnected-(J12-Pad16)") (class "Default")
      (node (ref "J12") (pin "16") (pinfunction "16_16") (pintype "passive"))
    )
    (net (code "176") (name "unconnected-(J12-Pad17)") (class "Default")
      (node (ref "J12") (pin "17") (pinfunction "17_17") (pintype "passive"))
    )
    (net (code "177") (name "unconnected-(J12-Pad18)") (class "Default")
      (node (ref "J12") (pin "18") (pinfunction "18_18") (pintype "passive"))
    )
    (net (code "178") (name "unconnected-(J13-Pad1)") (class "Default")
      (node (ref "J13") (pin "1") (pinfunction "1_1") (pintype "passive"))
    )
    (net (code "179") (name "unconnected-(J13-Pad2)") (class "Default")
      (node (ref "J13") (pin "2") (pinfunction "2_2") (pintype "passive"))
    )
    (net (code "180") (name "unconnected-(J13-Pad3)") (class "Default")
      (node (ref "J13") (pin "3") (pinfunction "3_3") (pintype "passive"))
    )
    (net (code "181") (name "unconnected-(J13-Pad4)") (class "Default")
      (node (ref "J13") (pin "4") (pinfunction "4_4") (pintype "passive"))
    )
    (net (code "182") (name "unconnected-(J13-Pad5)") (class "Default")
      (node (ref "J13") (pin "5") (pinfunction "5_5") (pintype "passive"))
    )
    (net (code "183") (name "unconnected-(J13-Pad6)") (class "Default")
      (node (ref "J13") (pin "6") (pinfunction "6_6") (pintype "passive"))
    )
    (net (code "184") (name "unconnected-(J13-Pad7)") (class "Default")
      (node (ref "J13") (pin "7") (pinfunction "7_7") (pintype "passive"))
    )
    (net (code "185") (name "unconnected-(J13-Pad8)") (class "Default")
      (node (ref "J13") (pin "8") (pinfunction "8_8") (pintype "passive"))
    )
    (net (code "186") (name "unconnected-(J13-Pad9)") (class "Default")
      (node (ref "J13") (pin "9") (pinfunction "9_9") (pintype "passive"))
    )
    (net (code "187") (name "unconnected-(J13-Pad10)") (class "Default")
      (node (ref "J13") (pin "10") (pinfunction "10_10") (pintype "passive"))
    )
    (net (code "188") (name "unconnected-(J13-Pad11)") (class "Default")
      (node (ref "J13") (pin "11") (pinfunction "11_11") (pintype "passive"))
    )
    (net (code "189") (name "unconnected-(J13-Pad12)") (class "Default")
      (node (ref "J13") (pin "12") (pinfunction "12_12") (pintype "passive"))
    )
    (net (code "190") (name "unconnected-(J13-Pad13)") (class "Default")
      (node (ref "J13") (pin "13") (pinfunction "13_13") (pintype "passive"))
    )
    (net (code "191") (name "unconnected-(J13-Pad14)") (class "Default")
      (node (ref "J13") (pin "14") (pinfunction "14_14") (pintype "passive"))
    )
    (net (code "192") (name "unconnected-(J13-Pad15)") (class "Default")
      (node (ref "J13") (pin "15") (pinfunction "15_15") (pintype "passive"))
    )
    (net (code "193") (name "unconnected-(J13-Pad16)") (class "Default")
      (node (ref "J13") (pin "16") (pinfunction "16_16") (pintype "passive"))
    )
    (net (code "194") (name "unconnected-(J13-Pad17)") (class "Default")
      (node (ref "J13") (pin "17") (pinfunction "17_17") (pintype "passive"))
    )
    (net (code "195") (name "unconnected-(J13-Pad18)") (class "Default")
      (node (ref "J13") (pin "18") (pinfunction "18_18") (pintype "passive"))
    )
    (net (code "196") (name "unconnected-(M1-AREF-PadJ2.13)") (class "Default")
      (node (ref "M1") (pin "J2.13") (pinfunction "AREF_J2.13") (pintype "bidirectional"))
    )
    (net (code "197") (name "unconnected-(M1-RST.1-PadJ1.3)") (class "Default")
      (node (ref "M1") (pin "J1.3") (pinfunction "RST.1_J1.3") (pintype "bidirectional"))
    )
    (net (code "198") (name "unconnected-(M1-RST.2-PadJ2.3)") (class "Default")
      (node (ref "M1") (pin "J2.3") (pinfunction "RST.2_J2.3") (pintype "bidirectional"))
    )
    (net (code "199") (name "unconnected-(S1-O-Pad1)") (class "Default")
      (node (ref "S1") (pin "1") (pinfunction "O_1") (pintype "passive"))
    )
  )
)
